# PreAmp.net
KiCad netlist of a schematic drawn in Altium Designer
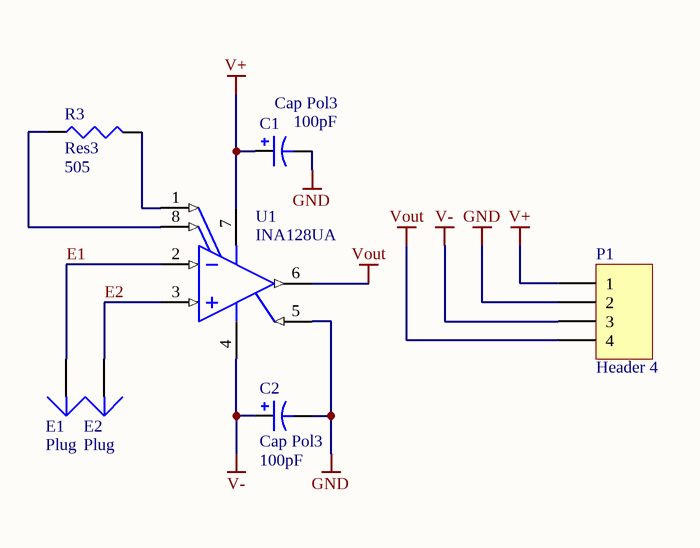
[diagram p0: PreAmp.SchDoc]

(export (version "E")
  (design (tool "Eeschema 10.0.6"))
  (components
    (comp (ref "C1")
      (value "Cap Pol3")
      (footprint "C0805")
      (description "Polarized Capacitor (Surface Mount)")
      (fields (field (name "ALTIUM_VALUE") "100pF") (field (name "PUBLISHER") "Altium Limited"))
      (libsource (lib "Miscellaneous Devices") (part "Cap Pol3"))
    )
    (comp (ref "C2")
      (value "Cap Pol3")
      (footprint "C0805")
      (description "Polarized Capacitor (Surface Mount)")
      (fields (field (name "ALTIUM_VALUE") "100pF") (field (name "PUBLISHER") "Altium Limited"))
      (libsource (lib "Miscellaneous Devices") (part "Cap Pol3"))
    )
    (comp (ref "E1")
      (value "Plug")
      (footprint "PIN1")
      (fields (field (name "PUBLISHER") "Altium Limited"))
      (libsource (lib "Miscellaneous Connectors") (part "Plug"))
    )
    (comp (ref "E2")
      (value "Plug")
      (footprint "PIN1")
      (fields (field (name "PUBLISHER") "Altium Limited"))
      (libsource (lib "Miscellaneous Connectors") (part "Plug"))
    )
    (comp (ref "P1")
      (value "Header 4")
      (footprint "HDR1X4")
      (description "Header, 4-Pin")
      (fields (field (name "PUBLISHER") "Altium Limited"))
      (libsource (lib "Miscellaneous Connectors") (part "Header 4"))
    )
    (comp (ref "R3")
      (value "Res3")
      (footprint "J1-0603")
      (description "Resistor")
      (fields (field (name "ALTIUM_VALUE") "505") (field (name "PUBLISHER") "Altium Limited"))
      (libsource (lib "Miscellaneous Devices") (part "Res3"))
    )
    (comp (ref "U1")
      (value "INA128UA")
      (footprint "TI-D8_N")
      (fields (field (name "MANUFACTURER") "Texas Instruments"))
      (libsource (lib "TI Amplifiers and Linear Instrumentation Amplifier") (part "INA128UA"))
    )
  )
  (nets
    (net (code "1") (name "/E1") (class "Default")
      (node (ref "E1") (pin "1") (pinfunction "1_1") (pintype "passive"))
      (node (ref "U1") (pin "2") (pinfunction "VIN-_2") (pintype "input"))
    )
    (net (code "2") (name "/E2") (class "Default")
      (node (ref "E2") (pin "1") (pinfunction "1_1") (pintype "passive"))
      (node (ref "U1") (pin "3") (pinfunction "VIN+_3") (pintype "input"))
    )
    (net (code "3") (name "GND") (class "Default")
      (node (ref "C1") (pin "2") (pinfunction "2_2") (pintype "passive"))
      (node (ref "C2") (pin "2") (pinfunction "2_2") (pintype "passive"))
      (node (ref "P1") (pin "2") (pinfunction "2_2") (pintype "passive"))
      (node (ref "U1") (pin "5") (pinfunction "REF_5") (pintype "input"))
    )
    (net (code "4") (name "Net-(R3-Pad1)") (class "Default")
      (node (ref "R3") (pin "1") (pinfunction "1_1") (pintype "passive"))
      (node (ref "U1") (pin "8") (pinfunction "RG_8") (pintype "input"))
    )
    (net (code "5") (name "Net-(R3-Pad2)") (class "Default")
      (node (ref "R3") (pin "2") (pinfunction "2_2") (pintype "passive"))
      (node (ref "U1") (pin "1") (pinfunction "RG_1") (pintype "input"))
    )
    (net (code "6") (name "V+") (class "Default")
      (node (ref "C1") (pin "1") (pinfunction "1_1") (pintype "passive"))
      (node (ref "P1") (pin "1") (pinfunction "1_1") (pintype "passive"))
      (node (ref "U1") (pin "7") (pinfunction "V+_7") (pintype "power_in"))
    )
    (net (code "7") (name "V-") (class "Default")
      (node (ref "C2") (pin "1") (pinfunction "1_1") (pintype "passive"))
      (node (ref "P1") (pin "3") (pinfunction "3_3") (pintype "passive"))
      (node (ref "U1") (pin "4") (pinfunction "V-_4") (pintype "power_in"))
    )
    (net (code "8") (name "Vout") (class "Default")
      (node (ref "P1") (pin "4") (pinfunction "4_4") (pintype "passive"))
      (node (ref "U1") (pin "6") (pinfunction "VO_6") (pintype "output"))
    )
  )
)
